# me433.net
KiCad netlist of a schematic drawn in EAGLE
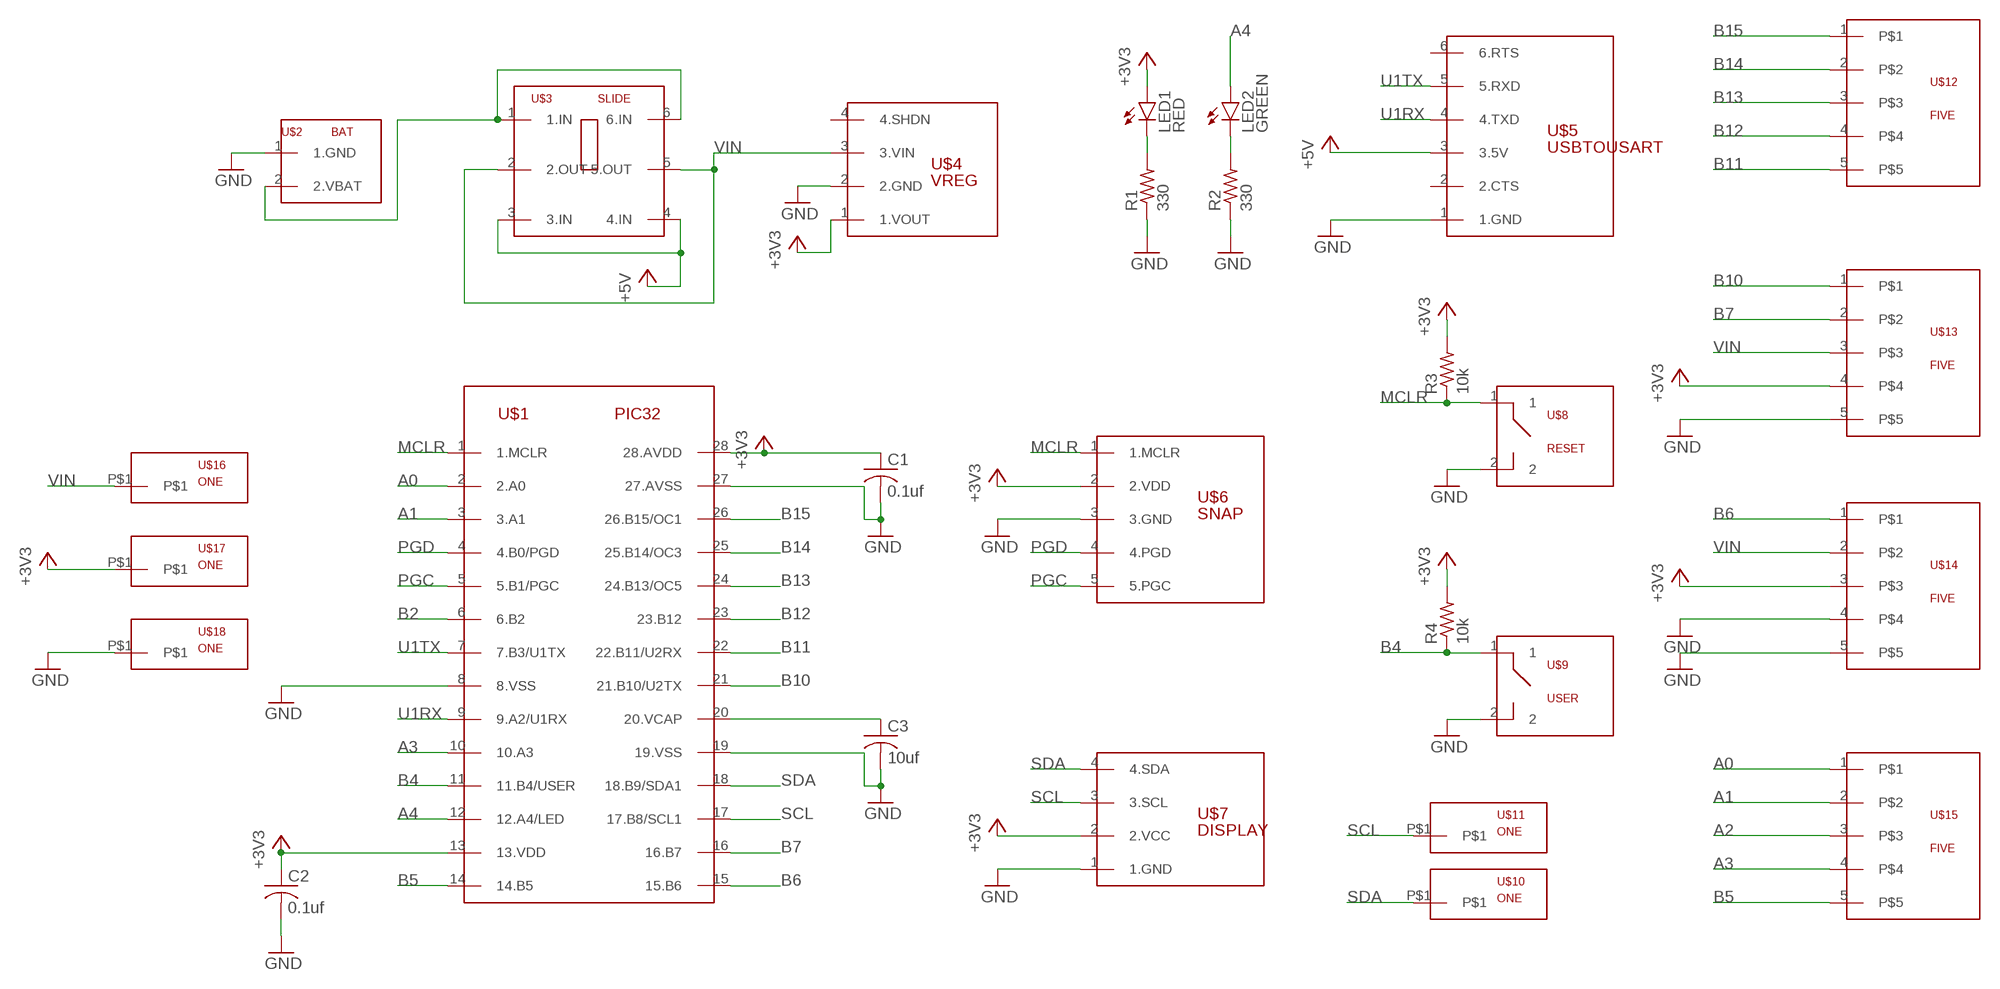
[diagram p0: schematic, sheet 1]

(export (version "E")
  (design (tool "Eeschema 10.0.6"))
  (components
    (comp (ref "C1")
      (value "0.1uf")
      (footprint "eagle-import:C025-024X044")
      (libsource (lib "eagle-import") (part "C-US025-024X044"))
    )
    (comp (ref "C2")
      (value "0.1uf")
      (footprint "eagle-import:C025-024X044")
      (libsource (lib "eagle-import") (part "C-US025-024X044"))
    )
    (comp (ref "C3")
      (value "10uf")
      (footprint "eagle-import:C025-024X044")
      (libsource (lib "eagle-import") (part "C-US025-024X044"))
    )
    (comp (ref "LED1")
      (value "RED")
      (footprint "eagle-import:LED3MM")
      (libsource (lib "eagle-import") (part "LED3MM"))
    )
    (comp (ref "LED2")
      (value "GREEN")
      (footprint "eagle-import:LED3MM")
      (libsource (lib "eagle-import") (part "LED3MM"))
    )
    (comp (ref "R1")
      (value "330")
      (footprint "eagle-import:0207_7")
      (libsource (lib "eagle-import") (part "R-US_0207/7"))
    )
    (comp (ref "R2")
      (value "330")
      (footprint "eagle-import:0207_7")
      (libsource (lib "eagle-import") (part "R-US_0207/7"))
    )
    (comp (ref "R3")
      (value "10k")
      (footprint "eagle-import:0207_7")
      (libsource (lib "eagle-import") (part "R-US_0207/7"))
    )
    (comp (ref "R4")
      (value "10k")
      (footprint "eagle-import:0207_7")
      (libsource (lib "eagle-import") (part "R-US_0207/7"))
    )
    (comp (ref "U$1")
      (value "PIC32")
      (footprint "eagle-import:DIL28-3")
      (libsource (lib "eagle-import") (part "PIC32"))
    )
    (comp (ref "U$2")
      (value "BAT")
      (footprint "eagle-import:BAT")
      (libsource (lib "eagle-import") (part "BAT"))
    )
    (comp (ref "U$3")
      (value "SLIDE")
      (footprint "eagle-import:SLIDE")
      (libsource (lib "eagle-import") (part "SLIDE"))
    )
    (comp (ref "U$4")
      (value "VREG")
      (footprint "eagle-import:VREG")
      (libsource (lib "eagle-import") (part "VREG"))
    )
    (comp (ref "U$5")
      (value "USBTOUSART")
      (footprint "eagle-import:USBTOUSART")
      (libsource (lib "eagle-import") (part "USBTOUSART"))
    )
    (comp (ref "U$6")
      (value "SNAP")
      (footprint "eagle-import:SNAP")
      (libsource (lib "eagle-import") (part "SNAP"))
    )
    (comp (ref "U$7")
      (value "DISPLAY")
      (footprint "eagle-import:DISPLAY")
      (libsource (lib "eagle-import") (part "DISPLAY"))
    )
    (comp (ref "U$8")
      (value "RESET")
      (footprint "eagle-import:BUTTON")
      (libsource (lib "eagle-import") (part "BUTTON"))
    )
    (comp (ref "U$9")
      (value "USER")
      (footprint "eagle-import:BUTTON")
      (libsource (lib "eagle-import") (part "BUTTON"))
    )
    (comp (ref "U$10")
      (value "ONE")
      (footprint "eagle-import:ONE")
      (libsource (lib "eagle-import") (part "ONE"))
    )
    (comp (ref "U$11")
      (value "ONE")
      (footprint "eagle-import:ONE")
      (libsource (lib "eagle-import") (part "ONE"))
    )
    (comp (ref "U$12")
      (value "FIVE")
      (footprint "eagle-import:FIVE")
      (libsource (lib "eagle-import") (part "FIVE"))
    )
    (comp (ref "U$13")
      (value "FIVE")
      (footprint "eagle-import:FIVE")
      (libsource (lib "eagle-import") (part "FIVE"))
    )
    (comp (ref "U$14")
      (value "FIVE")
      (footprint "eagle-import:FIVE")
      (libsource (lib "eagle-import") (part "FIVE"))
    )
    (comp (ref "U$15")
      (value "FIVE")
      (footprint "eagle-import:FIVE")
      (libsource (lib "eagle-import") (part "FIVE"))
    )
    (comp (ref "U$16")
      (value "ONE")
      (footprint "eagle-import:ONE")
      (libsource (lib "eagle-import") (part "ONE"))
    )
    (comp (ref "U$17")
      (value "ONE")
      (footprint "eagle-import:ONE")
      (libsource (lib "eagle-import") (part "ONE"))
    )
    (comp (ref "U$18")
      (value "ONE")
      (footprint "eagle-import:ONE")
      (libsource (lib "eagle-import") (part "ONE"))
    )
  )
  (nets
    (net (code "1") (name "+3V3") (class "Default")
      (node (ref "C1") (pin "1") (pinfunction "1_1") (pintype "passive"))
      (node (ref "C2") (pin "1") (pinfunction "1_1") (pintype "passive"))
      (node (ref "LED1") (pin "A") (pinfunction "A_A") (pintype "passive"))
      (node (ref "R3") (pin "2") (pinfunction "2_2") (pintype "passive"))
      (node (ref "R4") (pin "2") (pinfunction "2_2") (pintype "passive"))
      (node (ref "U$1") (pin "13") (pinfunction "13.VDD_13") (pintype "bidirectional"))
      (node (ref "U$1") (pin "28") (pinfunction "28.AVDD_28") (pintype "bidirectional"))
      (node (ref "U$13") (pin "4") (pinfunction "P$4_4") (pintype "bidirectional"))
      (node (ref "U$14") (pin "3") (pinfunction "P$3_3") (pintype "bidirectional"))
      (node (ref "U$17") (pin "P$1") (pinfunction "P$1_P$1") (pintype "bidirectional"))
      (node (ref "U$4") (pin "1") (pinfunction "1.VOUT_1") (pintype "bidirectional"))
      (node (ref "U$6") (pin "2") (pinfunction "2.VDD_2") (pintype "bidirectional"))
      (node (ref "U$7") (pin "2") (pinfunction "2.VCC_2") (pintype "bidirectional"))
    )
    (net (code "2") (name "+5V") (class "Default")
      (node (ref "U$3") (pin "3") (pinfunction "3.IN_3") (pintype "bidirectional"))
      (node (ref "U$3") (pin "4") (pinfunction "4.IN_4") (pintype "bidirectional"))
      (node (ref "U$5") (pin "3") (pinfunction "3.5V_3") (pintype "bidirectional"))
    )
    (net (code "3") (name "/A0") (class "Default")
      (node (ref "U$1") (pin "2") (pinfunction "2.A0_2") (pintype "bidirectional"))
      (node (ref "U$15") (pin "1") (pinfunction "P$1_1") (pintype "bidirectional"))
    )
    (net (code "4") (name "/A1") (class "Default")
      (node (ref "U$1") (pin "3") (pinfunction "3.A1_3") (pintype "bidirectional"))
      (node (ref "U$15") (pin "2") (pinfunction "P$2_2") (pintype "bidirectional"))
    )
    (net (code "5") (name "/A2") (class "Default")
      (node (ref "U$15") (pin "3") (pinfunction "P$3_3") (pintype "bidirectional"))
    )
    (net (code "6") (name "/A3") (class "Default")
      (node (ref "U$1") (pin "10") (pinfunction "10.A3_10") (pintype "bidirectional"))
      (node (ref "U$15") (pin "4") (pinfunction "P$4_4") (pintype "bidirectional"))
    )
    (net (code "7") (name "/A4") (class "Default")
      (node (ref "LED2") (pin "A") (pinfunction "A_A") (pintype "passive"))
      (node (ref "U$1") (pin "12") (pinfunction "12.A4/LED_12") (pintype "bidirectional"))
    )
    (net (code "8") (name "/B2") (class "Default")
      (node (ref "U$1") (pin "6") (pinfunction "6.B2_6") (pintype "bidirectional"))
    )
    (net (code "9") (name "/B4") (class "Default")
      (node (ref "R4") (pin "1") (pinfunction "1_1") (pintype "passive"))
      (node (ref "U$1") (pin "11") (pinfunction "11.B4/USER_11") (pintype "bidirectional"))
      (node (ref "U$9") (pin "1") (pinfunction "1_1") (pintype "bidirectional"))
    )
    (net (code "10") (name "/B5") (class "Default")
      (node (ref "U$1") (pin "14") (pinfunction "14.B5_14") (pintype "bidirectional"))
      (node (ref "U$15") (pin "5") (pinfunction "P$5_5") (pintype "bidirectional"))
    )
    (net (code "11") (name "/B6") (class "Default")
      (node (ref "U$1") (pin "15") (pinfunction "15.B6_15") (pintype "bidirectional"))
      (node (ref "U$14") (pin "1") (pinfunction "P$1_1") (pintype "bidirectional"))
    )
    (net (code "12") (name "/B7") (class "Default")
      (node (ref "U$1") (pin "16") (pinfunction "16.B7_16") (pintype "bidirectional"))
      (node (ref "U$13") (pin "2") (pinfunction "P$2_2") (pintype "bidirectional"))
    )
    (net (code "13") (name "/B10") (class "Default")
      (node (ref "U$1") (pin "21") (pinfunction "21.B10/U2TX_21") (pintype "bidirectional"))
      (node (ref "U$13") (pin "1") (pinfunction "P$1_1") (pintype "bidirectional"))
    )
    (net (code "14") (name "/B11") (class "Default")
      (node (ref "U$1") (pin "22") (pinfunction "22.B11/U2RX_22") (pintype "bidirectional"))
      (node (ref "U$12") (pin "5") (pinfunction "P$5_5") (pintype "bidirectional"))
    )
    (net (code "15") (name "/B12") (class "Default")
      (node (ref "U$1") (pin "23") (pinfunction "23.B12_23") (pintype "bidirectional"))
      (node (ref "U$12") (pin "4") (pinfunction "P$4_4") (pintype "bidirectional"))
    )
    (net (code "16") (name "/B13") (class "Default")
      (node (ref "U$1") (pin "24") (pinfunction "24.B13/OC5_24") (pintype "bidirectional"))
      (node (ref "U$12") (pin "3") (pinfunction "P$3_3") (pintype "bidirectional"))
    )
    (net (code "17") (name "/B14") (class "Default")
      (node (ref "U$1") (pin "25") (pinfunction "25.B14/OC3_25") (pintype "bidirectional"))
      (node (ref "U$12") (pin "2") (pinfunction "P$2_2") (pintype "bidirectional"))
    )
    (net (code "18") (name "/B15") (class "Default")
      (node (ref "U$1") (pin "26") (pinfunction "26.B15/OC1_26") (pintype "bidirectional"))
      (node (ref "U$12") (pin "1") (pinfunction "P$1_1") (pintype "bidirectional"))
    )
    (net (code "19") (name "/MCLR") (class "Default")
      (node (ref "R3") (pin "1") (pinfunction "1_1") (pintype "passive"))
      (node (ref "U$1") (pin "1") (pinfunction "1.MCLR_1") (pintype "bidirectional"))
      (node (ref "U$6") (pin "1") (pinfunction "1.MCLR_1") (pintype "bidirectional"))
      (node (ref "U$8") (pin "1") (pinfunction "1_1") (pintype "bidirectional"))
    )
    (net (code "20") (name "/PGC") (class "Default")
      (node (ref "U$1") (pin "5") (pinfunction "5.B1/PGC_5") (pintype "bidirectional"))
      (node (ref "U$6") (pin "5") (pinfunction "5.PGC_5") (pintype "bidirectional"))
    )
    (net (code "21") (name "/PGD") (class "Default")
      (node (ref "U$1") (pin "4") (pinfunction "4.B0/PGD_4") (pintype "bidirectional"))
      (node (ref "U$6") (pin "4") (pinfunction "4.PGD_4") (pintype "bidirectional"))
    )
    (net (code "22") (name "/SCL") (class "Default")
      (node (ref "U$1") (pin "17") (pinfunction "17.B8/SCL1_17") (pintype "bidirectional"))
      (node (ref "U$11") (pin "P$1") (pinfunction "P$1_P$1") (pintype "bidirectional"))
      (node (ref "U$7") (pin "3") (pinfunction "3.SCL_3") (pintype "bidirectional"))
    )
    (net (code "23") (name "/SDA") (class "Default")
      (node (ref "U$1") (pin "18") (pinfunction "18.B9/SDA1_18") (pintype "bidirectional"))
      (node (ref "U$10") (pin "P$1") (pinfunction "P$1_P$1") (pintype "bidirectional"))
      (node (ref "U$7") (pin "4") (pinfunction "4.SDA_4") (pintype "bidirectional"))
    )
    (net (code "24") (name "/U1RX") (class "Default")
      (node (ref "U$1") (pin "9") (pinfunction "9.A2/U1RX_9") (pintype "bidirectional"))
      (node (ref "U$5") (pin "4") (pinfunction "4.TXD_4") (pintype "bidirectional"))
    )
    (net (code "25") (name "/U1TX") (class "Default")
      (node (ref "U$1") (pin "7") (pinfunction "7.B3/U1TX_7") (pintype "bidirectional"))
      (node (ref "U$5") (pin "5") (pinfunction "5.RXD_5") (pintype "bidirectional"))
    )
    (net (code "26") (name "/VIN") (class "Default")
      (node (ref "U$13") (pin "3") (pinfunction "P$3_3") (pintype "bidirectional"))
      (node (ref "U$14") (pin "2") (pinfunction "P$2_2") (pintype "bidirectional"))
      (node (ref "U$16") (pin "P$1") (pinfunction "P$1_P$1") (pintype "bidirectional"))
      (node (ref "U$3") (pin "2") (pinfunction "2.OUT_2") (pintype "bidirectional"))
      (node (ref "U$3") (pin "5") (pinfunction "5.OUT_5") (pintype "bidirectional"))
      (node (ref "U$4") (pin "3") (pinfunction "3.VIN_3") (pintype "bidirectional"))
    )
    (net (code "27") (name "GND") (class "Default")
      (node (ref "C1") (pin "2") (pinfunction "2_2") (pintype "passive"))
      (node (ref "C2") (pin "2") (pinfunction "2_2") (pintype "passive"))
      (node (ref "C3") (pin "2") (pinfunction "2_2") (pintype "passive"))
      (node (ref "R1") (pin "1") (pinfunction "1_1") (pintype "passive"))
      (node (ref "R2") (pin "1") (pinfunction "1_1") (pintype "passive"))
      (node (ref "U$1") (pin "19") (pinfunction "19.VSS_19") (pintype "bidirectional"))
      (node (ref "U$1") (pin "27") (pinfunction "27.AVSS_27") (pintype "bidirectional"))
      (node (ref "U$1") (pin "8") (pinfunction "8.VSS_8") (pintype "bidirectional"))
      (node (ref "U$13") (pin "5") (pinfunction "P$5_5") (pintype "bidirectional"))
      (node (ref "U$14") (pin "4") (pinfunction "P$4_4") (pintype "bidirectional"))
      (node (ref "U$14") (pin "5") (pinfunction "P$5_5") (pintype "bidirectional"))
      (node (ref "U$18") (pin "P$1") (pinfunction "P$1_P$1") (pintype "bidirectional"))
      (node (ref "U$2") (pin "1") (pinfunction "1.GND_1") (pintype "bidirectional"))
      (node (ref "U$4") (pin "2") (pinfunction "2.GND_2") (pintype "bidirectional"))
      (node (ref "U$5") (pin "1") (pinfunction "1.GND_1") (pintype "bidirectional"))
      (node (ref "U$6") (pin "3") (pinfunction "3.GND_3") (pintype "bidirectional"))
      (node (ref "U$7") (pin "1") (pinfunction "1.GND_1") (pintype "bidirectional"))
      (node (ref "U$8") (pin "2") (pinfunction "2_2") (pintype "bidirectional"))
      (node (ref "U$9") (pin "2") (pinfunction "2_2") (pintype "bidirectional"))
    )
    (net (code "28") (name "Net-(LED1-C)") (class "Default")
      (node (ref "LED1") (pin "K") (pinfunction "C_K") (pintype "passive"))
      (node (ref "R1") (pin "2") (pinfunction "2_2") (pintype "passive"))
    )
    (net (code "29") (name "Net-(LED2-C)") (class "Default")
      (node (ref "LED2") (pin "K") (pinfunction "C_K") (pintype "passive"))
      (node (ref "R2") (pin "2") (pinfunction "2_2") (pintype "passive"))
    )
    (net (code "30") (name "Net-(U$1-20.VCAP)") (class "Default")
      (node (ref "C3") (pin "1") (pinfunction "1_1") (pintype "passive"))
      (node (ref "U$1") (pin "20") (pinfunction "20.VCAP_20") (pintype "bidirectional"))
    )
    (net (code "31") (name "Net-(U$2-2.VBAT)") (class "Default")
      (node (ref "U$2") (pin "2") (pinfunction "2.VBAT_2") (pintype "bidirectional"))
      (node (ref "U$3") (pin "1") (pinfunction "1.IN_1") (pintype "bidirectional"))
      (node (ref "U$3") (pin "6") (pinfunction "6.IN_6") (pintype "bidirectional"))
    )
    (net (code "32") (name "unconnected-(U$4-4.SHDN-Pad4)") (class "Default")
      (node (ref "U$4") (pin "4") (pinfunction "4.SHDN_4") (pintype "bidirectional"))
    )
    (net (code "33") (name "unconnected-(U$5-2.CTS-Pad2)") (class "Default")
      (node (ref "U$5") (pin "2") (pinfunction "2.CTS_2") (pintype "bidirectional"))
    )
    (net (code "34") (name "unconnected-(U$5-6.RTS-Pad6)") (class "Default")
      (node (ref "U$5") (pin "6") (pinfunction "6.RTS_6") (pintype "bidirectional"))
    )
  )
)
